# M516.net
KiCad netlist of a schematic drawn in EAGLE
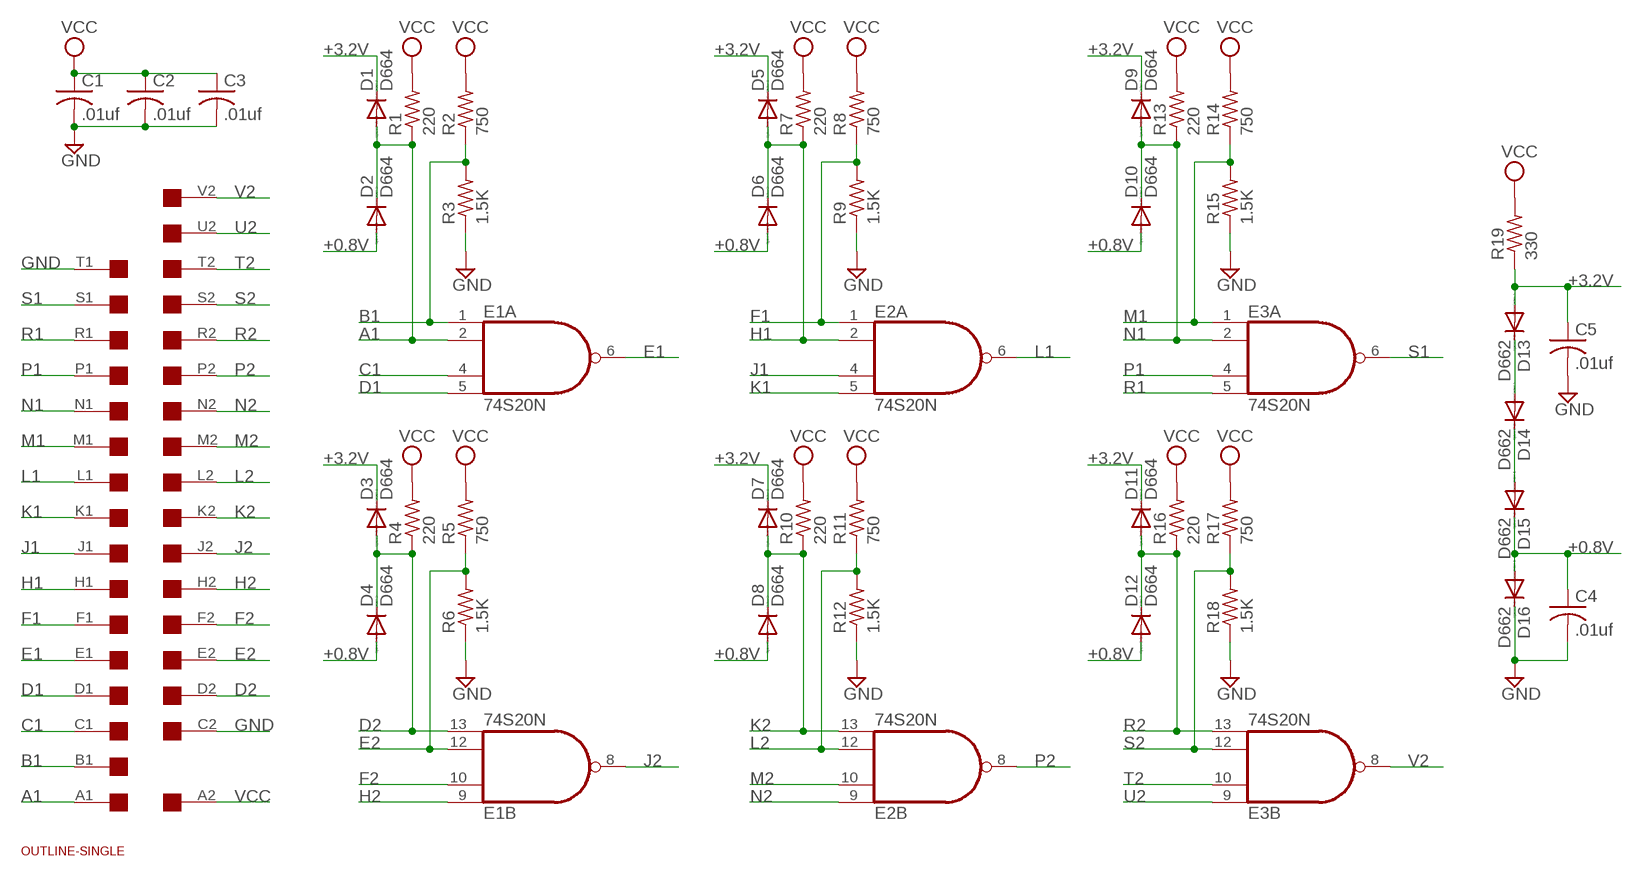
[diagram p0: schematic, sheet 1]

(export (version "E")
  (design (tool "Eeschema 10.0.6"))
  (components
    (comp (ref "C1")
      (value ".01uf")
      (footprint "eagle-import:C050-025X075")
      (libsource (lib "eagle-import") (part "C-US050-025X075"))
    )
    (comp (ref "C2")
      (value ".01uf")
      (footprint "eagle-import:C050-025X075")
      (libsource (lib "eagle-import") (part "C-US050-025X075"))
    )
    (comp (ref "C3")
      (value ".01uf")
      (footprint "eagle-import:C050-025X075")
      (libsource (lib "eagle-import") (part "C-US050-025X075"))
    )
    (comp (ref "C4")
      (value ".01uf")
      (footprint "eagle-import:C050-025X075")
      (libsource (lib "eagle-import") (part "C-US050-025X075"))
    )
    (comp (ref "C5")
      (value ".01uf")
      (footprint "eagle-import:C050-025X075")
      (libsource (lib "eagle-import") (part "C-US050-025X075"))
    )
    (comp (ref "D1")
      (value "D664")
      (footprint "eagle-import:DO35-10")
      (libsource (lib "eagle-import") (part "1N4148DO35-10"))
    )
    (comp (ref "D2")
      (value "D664")
      (footprint "eagle-import:DO35-10")
      (libsource (lib "eagle-import") (part "1N4148DO35-10"))
    )
    (comp (ref "D3")
      (value "D664")
      (footprint "eagle-import:DO35-10")
      (libsource (lib "eagle-import") (part "1N4148DO35-10"))
    )
    (comp (ref "D4")
      (value "D664")
      (footprint "eagle-import:DO35-10")
      (libsource (lib "eagle-import") (part "1N4148DO35-10"))
    )
    (comp (ref "D5")
      (value "D664")
      (footprint "eagle-import:DO35-10")
      (libsource (lib "eagle-import") (part "1N4148DO35-10"))
    )
    (comp (ref "D6")
      (value "D664")
      (footprint "eagle-import:DO35-10")
      (libsource (lib "eagle-import") (part "1N4148DO35-10"))
    )
    (comp (ref "D7")
      (value "D664")
      (footprint "eagle-import:DO35-10")
      (libsource (lib "eagle-import") (part "1N4148DO35-10"))
    )
    (comp (ref "D8")
      (value "D664")
      (footprint "eagle-import:DO35-10")
      (libsource (lib "eagle-import") (part "1N4148DO35-10"))
    )
    (comp (ref "D9")
      (value "D664")
      (footprint "eagle-import:DO35-10")
      (libsource (lib "eagle-import") (part "1N4148DO35-10"))
    )
    (comp (ref "D10")
      (value "D664")
      (footprint "eagle-import:DO35-10")
      (libsource (lib "eagle-import") (part "1N4148DO35-10"))
    )
    (comp (ref "D11")
      (value "D664")
      (footprint "eagle-import:DO35-10")
      (libsource (lib "eagle-import") (part "1N4148DO35-10"))
    )
    (comp (ref "D12")
      (value "D664")
      (footprint "eagle-import:DO35-10")
      (libsource (lib "eagle-import") (part "1N4148DO35-10"))
    )
    (comp (ref "D13")
      (value "D662")
      (footprint "eagle-import:DO35-10")
      (libsource (lib "eagle-import") (part "1N4148DO35-10"))
    )
    (comp (ref "D14")
      (value "D662")
      (footprint "eagle-import:DO35-10")
      (libsource (lib "eagle-import") (part "1N4148DO35-10"))
    )
    (comp (ref "D15")
      (value "D662")
      (footprint "eagle-import:DO35-10")
      (libsource (lib "eagle-import") (part "1N4148DO35-10"))
    )
    (comp (ref "D16")
      (value "D662")
      (footprint "eagle-import:DO35-10")
      (libsource (lib "eagle-import") (part "1N4148DO35-10"))
    )
    (comp (ref "E1")
      (value "74S20N")
      (footprint "eagle-import:DIL14")
      (libsource (lib "eagle-import") (part "7420NS"))
    )
    (comp (ref "E2")
      (value "74S20N")
      (footprint "eagle-import:DIL14")
      (libsource (lib "eagle-import") (part "7420NS"))
    )
    (comp (ref "E3")
      (value "74S20N")
      (footprint "eagle-import:DIL14")
      (libsource (lib "eagle-import") (part "7420NS"))
    )
    (comp (ref "R1")
      (value "220")
      (footprint "eagle-import:0207_10")
      (libsource (lib "eagle-import") (part "R-US_0207/10"))
    )
    (comp (ref "R2")
      (value "750")
      (footprint "eagle-import:0207_10")
      (libsource (lib "eagle-import") (part "R-US_0207/10"))
    )
    (comp (ref "R3")
      (value "1.5K")
      (footprint "eagle-import:0207_10")
      (libsource (lib "eagle-import") (part "R-US_0207/10"))
    )
    (comp (ref "R4")
      (value "220")
      (footprint "eagle-import:0207_10")
      (libsource (lib "eagle-import") (part "R-US_0207/10"))
    )
    (comp (ref "R5")
      (value "750")
      (footprint "eagle-import:0207_10")
      (libsource (lib "eagle-import") (part "R-US_0207/10"))
    )
    (comp (ref "R6")
      (value "1.5K")
      (footprint "eagle-import:0207_10")
      (libsource (lib "eagle-import") (part "R-US_0207/10"))
    )
    (comp (ref "R7")
      (value "220")
      (footprint "eagle-import:0207_10")
      (libsource (lib "eagle-import") (part "R-US_0207/10"))
    )
    (comp (ref "R8")
      (value "750")
      (footprint "eagle-import:0207_10")
      (libsource (lib "eagle-import") (part "R-US_0207/10"))
    )
    (comp (ref "R9")
      (value "1.5K")
      (footprint "eagle-import:0207_10")
      (libsource (lib "eagle-import") (part "R-US_0207/10"))
    )
    (comp (ref "R10")
      (value "220")
      (footprint "eagle-import:0207_10")
      (libsource (lib "eagle-import") (part "R-US_0207/10"))
    )
    (comp (ref "R11")
      (value "750")
      (footprint "eagle-import:0207_10")
      (libsource (lib "eagle-import") (part "R-US_0207/10"))
    )
    (comp (ref "R12")
      (value "1.5K")
      (footprint "eagle-import:0207_10")
      (libsource (lib "eagle-import") (part "R-US_0207/10"))
    )
    (comp (ref "R13")
      (value "220")
      (footprint "eagle-import:0207_10")
      (libsource (lib "eagle-import") (part "R-US_0207/10"))
    )
    (comp (ref "R14")
      (value "750")
      (footprint "eagle-import:0207_10")
      (libsource (lib "eagle-import") (part "R-US_0207/10"))
    )
    (comp (ref "R15")
      (value "1.5K")
      (footprint "eagle-import:0207_10")
      (libsource (lib "eagle-import") (part "R-US_0207/10"))
    )
    (comp (ref "R16")
      (value "220")
      (footprint "eagle-import:0207_10")
      (libsource (lib "eagle-import") (part "R-US_0207/10"))
    )
    (comp (ref "R17")
      (value "750")
      (footprint "eagle-import:0207_10")
      (libsource (lib "eagle-import") (part "R-US_0207/10"))
    )
    (comp (ref "R18")
      (value "1.5K")
      (footprint "eagle-import:0207_10")
      (libsource (lib "eagle-import") (part "R-US_0207/10"))
    )
    (comp (ref "R19")
      (value "330")
      (footprint "eagle-import:0207_10")
      (libsource (lib "eagle-import") (part "R-US_0207/10"))
    )
    (comp (ref "U$1")
      (value "OUTLINE-SINGLE")
      (footprint "eagle-import:SINGLE")
      (libsource (lib "eagle-import") (part "OUTLINE-SINGLE"))
    )
    (comp (ref "U$2")
      (value "SINGLE")
      (footprint "eagle-import:EDGE-CON2")
      (libsource (lib "eagle-import") (part "SINGLE"))
    )
  )
  (nets
    (net (code "1") (name "/+0.8V") (class "Default")
      (node (ref "C4") (pin "1") (pinfunction "1_1") (pintype "passive"))
      (node (ref "D10") (pin "A") (pinfunction "A_A") (pintype "passive"))
      (node (ref "D12") (pin "A") (pinfunction "A_A") (pintype "passive"))
      (node (ref "D15") (pin "C") (pinfunction "C_C") (pintype "passive"))
      (node (ref "D16") (pin "A") (pinfunction "A_A") (pintype "passive"))
      (node (ref "D2") (pin "A") (pinfunction "A_A") (pintype "passive"))
      (node (ref "D4") (pin "A") (pinfunction "A_A") (pintype "passive"))
      (node (ref "D6") (pin "A") (pinfunction "A_A") (pintype "passive"))
      (node (ref "D8") (pin "A") (pinfunction "A_A") (pintype "passive"))
    )
    (net (code "2") (name "/+3.2V") (class "Default")
      (node (ref "C5") (pin "1") (pinfunction "1_1") (pintype "passive"))
      (node (ref "D1") (pin "C") (pinfunction "C_C") (pintype "passive"))
      (node (ref "D11") (pin "C") (pinfunction "C_C") (pintype "passive"))
      (node (ref "D13") (pin "A") (pinfunction "A_A") (pintype "passive"))
      (node (ref "D3") (pin "C") (pinfunction "C_C") (pintype "passive"))
      (node (ref "D5") (pin "C") (pinfunction "C_C") (pintype "passive"))
      (node (ref "D7") (pin "C") (pinfunction "C_C") (pintype "passive"))
      (node (ref "D9") (pin "C") (pinfunction "C_C") (pintype "passive"))
      (node (ref "R19") (pin "1") (pinfunction "1_1") (pintype "passive"))
    )
    (net (code "3") (name "/A1") (class "Default")
      (node (ref "D1") (pin "A") (pinfunction "A_A") (pintype "passive"))
      (node (ref "D2") (pin "C") (pinfunction "C_C") (pintype "passive"))
      (node (ref "E1") (pin "2") (pinfunction "I1_2") (pintype "input"))
      (node (ref "R1") (pin "1") (pinfunction "1_1") (pintype "passive"))
      (node (ref "U$2") (pin "A1") (pinfunction "1_A1") (pintype "bidirectional"))
    )
    (net (code "4") (name "/B1") (class "Default")
      (node (ref "E1") (pin "1") (pinfunction "I0_1") (pintype "input"))
      (node (ref "R2") (pin "1") (pinfunction "1_1") (pintype "passive"))
      (node (ref "R3") (pin "2") (pinfunction "2_2") (pintype "passive"))
      (node (ref "U$2") (pin "B1") (pinfunction "1_B1") (pintype "bidirectional"))
    )
    (net (code "5") (name "/C1") (class "Default")
      (node (ref "E1") (pin "4") (pinfunction "I2_4") (pintype "input"))
      (node (ref "U$2") (pin "C1") (pinfunction "1_C1") (pintype "bidirectional"))
    )
    (net (code "6") (name "/D1") (class "Default")
      (node (ref "E1") (pin "5") (pinfunction "I3_5") (pintype "input"))
      (node (ref "U$2") (pin "D1") (pinfunction "1_D1") (pintype "bidirectional"))
    )
    (net (code "7") (name "/D2") (class "Default")
      (node (ref "D3") (pin "A") (pinfunction "A_A") (pintype "passive"))
      (node (ref "D4") (pin "C") (pinfunction "C_C") (pintype "passive"))
      (node (ref "E1") (pin "13") (pinfunction "I3_13") (pintype "input"))
      (node (ref "R4") (pin "1") (pinfunction "1_1") (pintype "passive"))
      (node (ref "U$2") (pin "D2") (pinfunction "1_D2") (pintype "bidirectional"))
    )
    (net (code "8") (name "/E1") (class "Default")
      (node (ref "E1") (pin "6") (pinfunction "O_6") (pintype "output"))
      (node (ref "U$2") (pin "E1") (pinfunction "1_E1") (pintype "bidirectional"))
    )
    (net (code "9") (name "/E2") (class "Default")
      (node (ref "E1") (pin "12") (pinfunction "I2_12") (pintype "input"))
      (node (ref "R5") (pin "1") (pinfunction "1_1") (pintype "passive"))
      (node (ref "R6") (pin "2") (pinfunction "2_2") (pintype "passive"))
      (node (ref "U$2") (pin "E2") (pinfunction "1_E2") (pintype "bidirectional"))
    )
    (net (code "10") (name "/F1") (class "Default")
      (node (ref "E2") (pin "1") (pinfunction "I0_1") (pintype "input"))
      (node (ref "R8") (pin "1") (pinfunction "1_1") (pintype "passive"))
      (node (ref "R9") (pin "2") (pinfunction "2_2") (pintype "passive"))
      (node (ref "U$2") (pin "F1") (pinfunction "1_F1") (pintype "bidirectional"))
    )
    (net (code "11") (name "/F2") (class "Default")
      (node (ref "E1") (pin "10") (pinfunction "I1_10") (pintype "input"))
      (node (ref "U$2") (pin "F2") (pinfunction "1_F2") (pintype "bidirectional"))
    )
    (net (code "12") (name "/H1") (class "Default")
      (node (ref "D5") (pin "A") (pinfunction "A_A") (pintype "passive"))
      (node (ref "D6") (pin "C") (pinfunction "C_C") (pintype "passive"))
      (node (ref "E2") (pin "2") (pinfunction "I1_2") (pintype "input"))
      (node (ref "R7") (pin "1") (pinfunction "1_1") (pintype "passive"))
      (node (ref "U$2") (pin "H1") (pinfunction "1_H1") (pintype "bidirectional"))
    )
    (net (code "13") (name "/H2") (class "Default")
      (node (ref "E1") (pin "9") (pinfunction "I0_9") (pintype "input"))
      (node (ref "U$2") (pin "H2") (pinfunction "1_H2") (pintype "bidirectional"))
    )
    (net (code "14") (name "/J1") (class "Default")
      (node (ref "E2") (pin "4") (pinfunction "I2_4") (pintype "input"))
      (node (ref "U$2") (pin "J1") (pinfunction "1_J1") (pintype "bidirectional"))
    )
    (net (code "15") (name "/J2") (class "Default")
      (node (ref "E1") (pin "8") (pinfunction "O_8") (pintype "output"))
      (node (ref "U$2") (pin "J2") (pinfunction "1_J2") (pintype "bidirectional"))
    )
    (net (code "16") (name "/K1") (class "Default")
      (node (ref "E2") (pin "5") (pinfunction "I3_5") (pintype "input"))
      (node (ref "U$2") (pin "K1") (pinfunction "1_K1") (pintype "bidirectional"))
    )
    (net (code "17") (name "/K2") (class "Default")
      (node (ref "D7") (pin "A") (pinfunction "A_A") (pintype "passive"))
      (node (ref "D8") (pin "C") (pinfunction "C_C") (pintype "passive"))
      (node (ref "E2") (pin "13") (pinfunction "I3_13") (pintype "input"))
      (node (ref "R10") (pin "1") (pinfunction "1_1") (pintype "passive"))
      (node (ref "U$2") (pin "K2") (pinfunction "1_K2") (pintype "bidirectional"))
    )
    (net (code "18") (name "/L1") (class "Default")
      (node (ref "E2") (pin "6") (pinfunction "O_6") (pintype "output"))
      (node (ref "U$2") (pin "L1") (pinfunction "1_L1") (pintype "bidirectional"))
    )
    (net (code "19") (name "/L2") (class "Default")
      (node (ref "E2") (pin "12") (pinfunction "I2_12") (pintype "input"))
      (node (ref "R11") (pin "1") (pinfunction "1_1") (pintype "passive"))
      (node (ref "R12") (pin "2") (pinfunction "2_2") (pintype "passive"))
      (node (ref "U$2") (pin "L2") (pinfunction "1_L2") (pintype "bidirectional"))
    )
    (net (code "20") (name "/M1") (class "Default")
      (node (ref "E3") (pin "1") (pinfunction "I0_1") (pintype "input"))
      (node (ref "R14") (pin "1") (pinfunction "1_1") (pintype "passive"))
      (node (ref "R15") (pin "2") (pinfunction "2_2") (pintype "passive"))
      (node (ref "U$2") (pin "M1") (pinfunction "1_M1") (pintype "bidirectional"))
    )
    (net (code "21") (name "/M2") (class "Default")
      (node (ref "E2") (pin "10") (pinfunction "I1_10") (pintype "input"))
      (node (ref "U$2") (pin "M2") (pinfunction "1_M2") (pintype "bidirectional"))
    )
    (net (code "22") (name "/N1") (class "Default")
      (node (ref "D10") (pin "C") (pinfunction "C_C") (pintype "passive"))
      (node (ref "D9") (pin "A") (pinfunction "A_A") (pintype "passive"))
      (node (ref "E3") (pin "2") (pinfunction "I1_2") (pintype "input"))
      (node (ref "R13") (pin "1") (pinfunction "1_1") (pintype "passive"))
      (node (ref "U$2") (pin "N1") (pinfunction "1_N1") (pintype "bidirectional"))
    )
    (net (code "23") (name "/N2") (class "Default")
      (node (ref "E2") (pin "9") (pinfunction "I0_9") (pintype "input"))
      (node (ref "U$2") (pin "N2") (pinfunction "1_N2") (pintype "bidirectional"))
    )
    (net (code "24") (name "/P1") (class "Default")
      (node (ref "E3") (pin "4") (pinfunction "I2_4") (pintype "input"))
      (node (ref "U$2") (pin "P1") (pinfunction "1_P1") (pintype "bidirectional"))
    )
    (net (code "25") (name "/P2") (class "Default")
      (node (ref "E2") (pin "8") (pinfunction "O_8") (pintype "output"))
      (node (ref "U$2") (pin "P2") (pinfunction "1_P2") (pintype "bidirectional"))
    )
    (net (code "26") (name "/R1") (class "Default")
      (node (ref "E3") (pin "5") (pinfunction "I3_5") (pintype "input"))
      (node (ref "U$2") (pin "R1") (pinfunction "1_R1") (pintype "bidirectional"))
    )
    (net (code "27") (name "/R2") (class "Default")
      (node (ref "D11") (pin "A") (pinfunction "A_A") (pintype "passive"))
      (node (ref "D12") (pin "C") (pinfunction "C_C") (pintype "passive"))
      (node (ref "E3") (pin "13") (pinfunction "I3_13") (pintype "input"))
      (node (ref "R16") (pin "1") (pinfunction "1_1") (pintype "passive"))
      (node (ref "U$2") (pin "R2") (pinfunction "1_R2") (pintype "bidirectional"))
    )
    (net (code "28") (name "/S1") (class "Default")
      (node (ref "E3") (pin "6") (pinfunction "O_6") (pintype "output"))
      (node (ref "U$2") (pin "S1") (pinfunction "1_S1") (pintype "bidirectional"))
    )
    (net (code "29") (name "/S2") (class "Default")
      (node (ref "E3") (pin "12") (pinfunction "I2_12") (pintype "input"))
      (node (ref "R17") (pin "1") (pinfunction "1_1") (pintype "passive"))
      (node (ref "R18") (pin "2") (pinfunction "2_2") (pintype "passive"))
      (node (ref "U$2") (pin "S2") (pinfunction "1_S2") (pintype "bidirectional"))
    )
    (net (code "30") (name "/T2") (class "Default")
      (node (ref "E3") (pin "10") (pinfunction "I1_10") (pintype "input"))
      (node (ref "U$2") (pin "T2") (pinfunction "1_T2") (pintype "bidirectional"))
    )
    (net (code "31") (name "/U2") (class "Default")
      (node (ref "E3") (pin "9") (pinfunction "I0_9") (pintype "input"))
      (node (ref "U$2") (pin "U2") (pinfunction "1_U2") (pintype "bidirectional"))
    )
    (net (code "32") (name "/V2") (class "Default")
      (node (ref "E3") (pin "8") (pinfunction "O_8") (pintype "output"))
      (node (ref "U$2") (pin "V2") (pinfunction "1_V2") (pintype "bidirectional"))
    )
    (net (code "33") (name "GND") (class "Default")
      (node (ref "C1") (pin "2") (pinfunction "2_2") (pintype "passive"))
      (node (ref "C2") (pin "2") (pinfunction "2_2") (pintype "passive"))
      (node (ref "C3") (pin "2") (pinfunction "2_2") (pintype "passive"))
      (node (ref "C4") (pin "2") (pinfunction "2_2") (pintype "passive"))
      (node (ref "C5") (pin "2") (pinfunction "2_2") (pintype "passive"))
      (node (ref "D16") (pin "C") (pinfunction "C_C") (pintype "passive"))
      (node (ref "R12") (pin "1") (pinfunction "1_1") (pintype "passive"))
      (node (ref "R15") (pin "1") (pinfunction "1_1") (pintype "passive"))
      (node (ref "R18") (pin "1") (pinfunction "1_1") (pintype "passive"))
      (node (ref "R3") (pin "1") (pinfunction "1_1") (pintype "passive"))
      (node (ref "R6") (pin "1") (pinfunction "1_1") (pintype "passive"))
      (node (ref "R9") (pin "1") (pinfunction "1_1") (pintype "passive"))
      (node (ref "U$2") (pin "C2") (pinfunction "1_C2") (pintype "bidirectional"))
      (node (ref "U$2") (pin "T1") (pinfunction "1_T1") (pintype "bidirectional"))
    )
    (net (code "34") (name "Net-(D13-PadC)") (class "Default")
      (node (ref "D13") (pin "C") (pinfunction "C_C") (pintype "passive"))
      (node (ref "D14") (pin "A") (pinfunction "A_A") (pintype "passive"))
    )
    (net (code "35") (name "Net-(D14-PadC)") (class "Default")
      (node (ref "D14") (pin "C") (pinfunction "C_C") (pintype "passive"))
      (node (ref "D15") (pin "A") (pinfunction "A_A") (pintype "passive"))
    )
    (net (code "36") (name "VCC") (class "Default")
      (node (ref "C1") (pin "1") (pinfunction "1_1") (pintype "passive"))
      (node (ref "C2") (pin "1") (pinfunction "1_1") (pintype "passive"))
      (node (ref "C3") (pin "1") (pinfunction "1_1") (pintype "passive"))
      (node (ref "R1") (pin "2") (pinfunction "2_2") (pintype "passive"))
      (node (ref "R10") (pin "2") (pinfunction "2_2") (pintype "passive"))
      (node (ref "R11") (pin "2") (pinfunction "2_2") (pintype "passive"))
      (node (ref "R13") (pin "2") (pinfunction "2_2") (pintype "passive"))
      (node (ref "R14") (pin "2") (pinfunction "2_2") (pintype "passive"))
      (node (ref "R16") (pin "2") (pinfunction "2_2") (pintype "passive"))
      (node (ref "R17") (pin "2") (pinfunction "2_2") (pintype "passive"))
      (node (ref "R19") (pin "2") (pinfunction "2_2") (pintype "passive"))
      (node (ref "R2") (pin "2") (pinfunction "2_2") (pintype "passive"))
      (node (ref "R4") (pin "2") (pinfunction "2_2") (pintype "passive"))
      (node (ref "R5") (pin "2") (pinfunction "2_2") (pintype "passive"))
      (node (ref "R7") (pin "2") (pinfunction "2_2") (pintype "passive"))
      (node (ref "R8") (pin "2") (pinfunction "2_2") (pintype "passive"))
      (node (ref "U$2") (pin "A2") (pinfunction "1_A2") (pintype "bidirectional"))
    )
  )
)
